# PIC-adresseur_-_SuperCAST.net
KiCad netlist of a schematic drawn in EAGLE
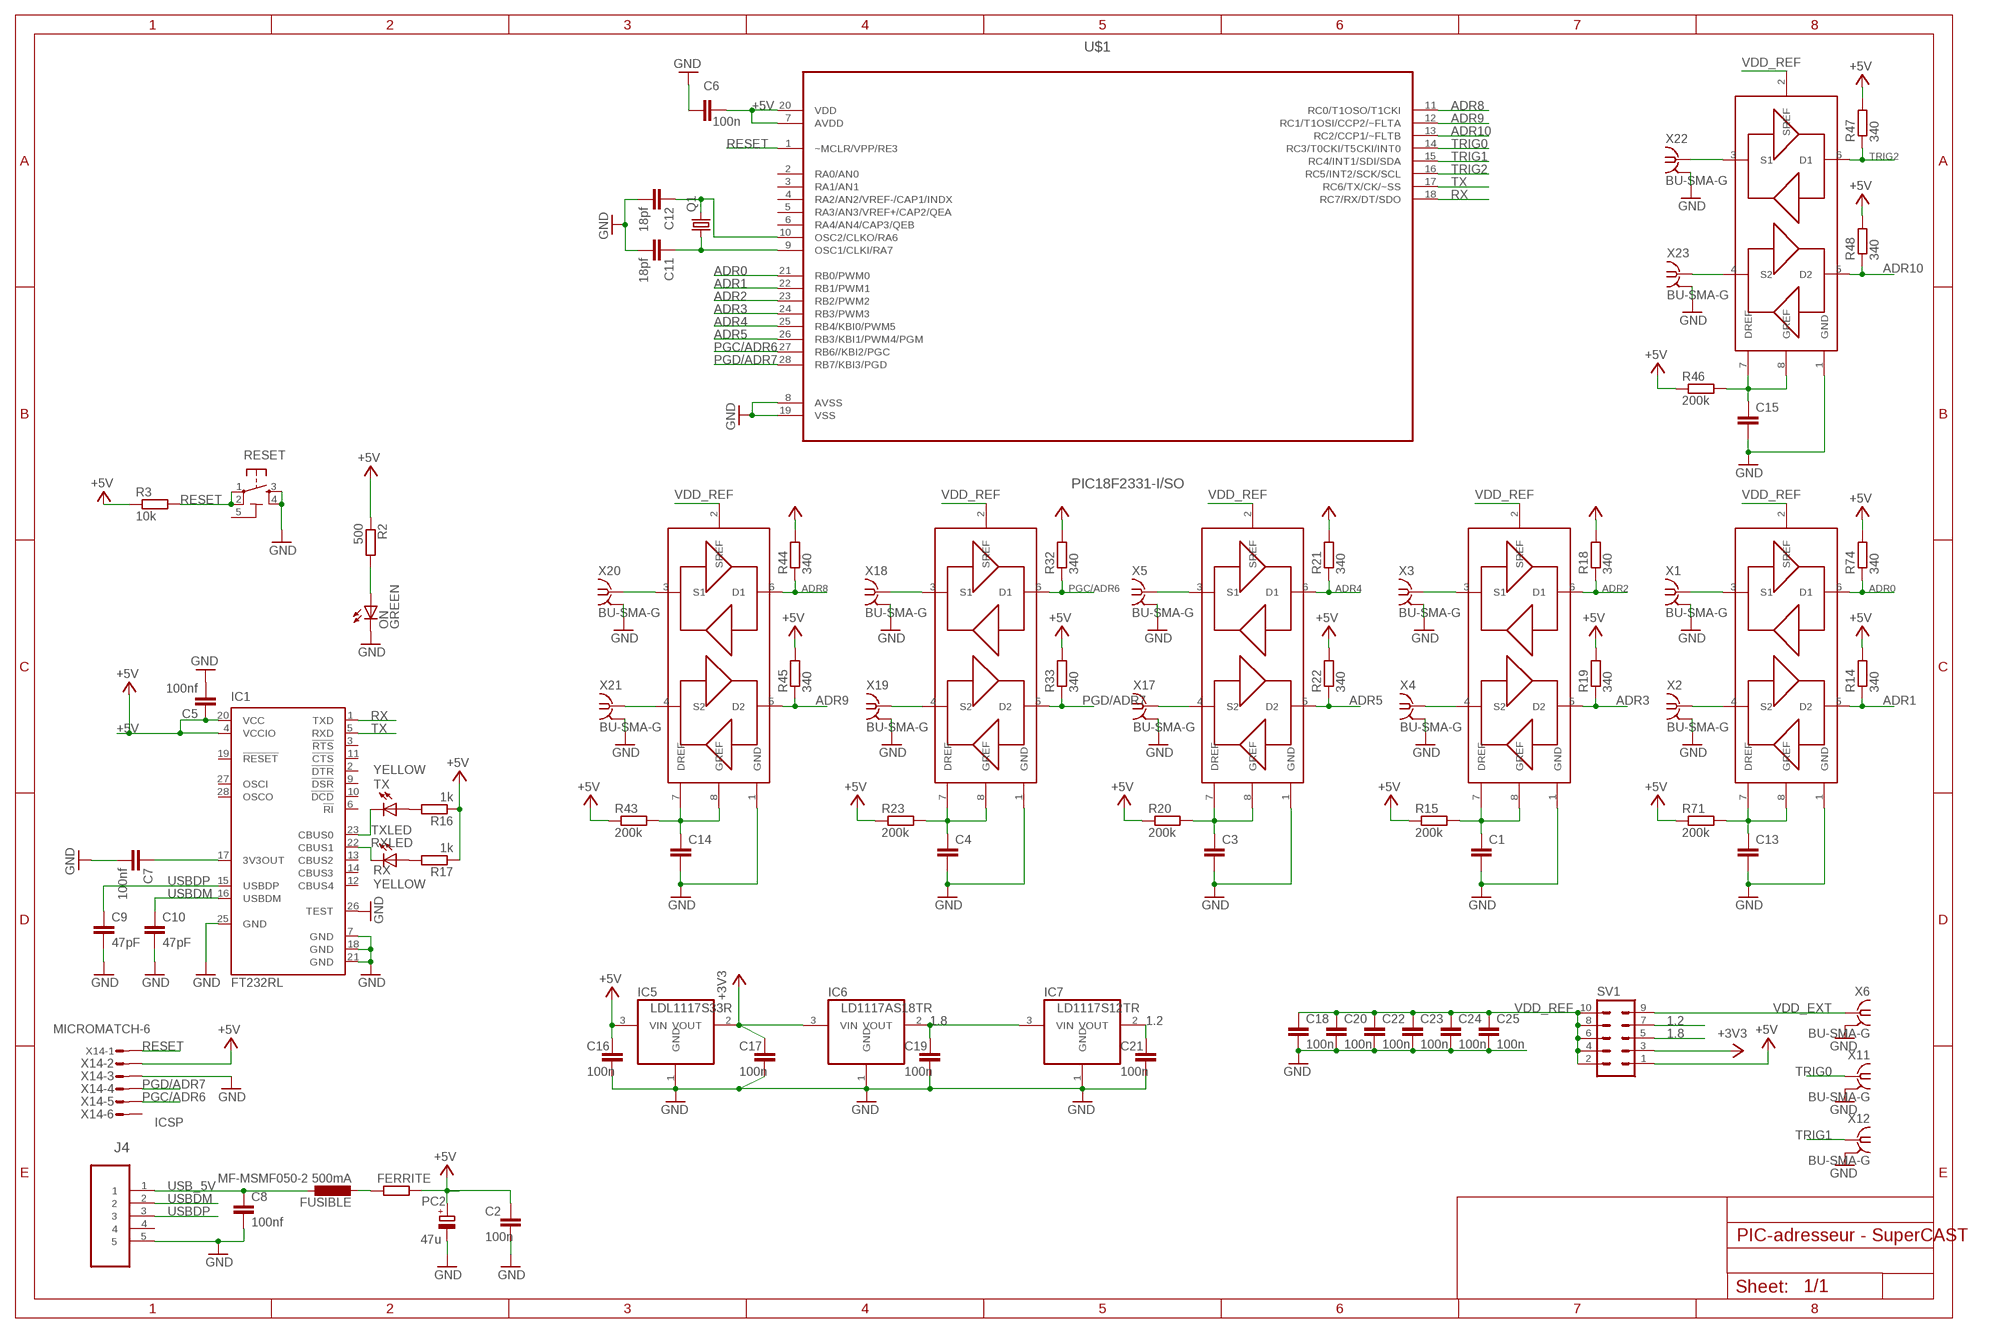
[diagram p0: schematic, sheet 1]

(export (version "E")
  (design (tool "Eeschema 10.0.6"))
  (components
    (comp (ref "C1")
      (value "C-EUC0603")
      (footprint "eagle-import:C0603")
      (libsource (lib "eagle-import") (part "rcl_334_C-EUC0603"))
    )
    (comp (ref "C2")
      (value "100n")
      (footprint "eagle-import:C0603-ROUND")
      (libsource (lib "eagle-import") (part "C-EU0603-RND"))
    )
    (comp (ref "C3")
      (value "C-EUC0603")
      (footprint "eagle-import:C0603")
      (libsource (lib "eagle-import") (part "rcl_334_C-EUC0603"))
    )
    (comp (ref "C4")
      (value "C-EUC0603")
      (footprint "eagle-import:C0603")
      (libsource (lib "eagle-import") (part "rcl_334_C-EUC0603"))
    )
    (comp (ref "C5")
      (value "100nf")
      (footprint "eagle-import:C0603")
      (libsource (lib "eagle-import") (part "C-EUC0603"))
    )
    (comp (ref "C6")
      (value "100n")
      (footprint "eagle-import:C0603K")
      (libsource (lib "eagle-import") (part "SmartPrj_C-EUC0603K"))
    )
    (comp (ref "C7")
      (value "100nf")
      (footprint "eagle-import:C0603")
      (libsource (lib "eagle-import") (part "C-EUC0603"))
    )
    (comp (ref "C8")
      (value "100nf")
      (footprint "eagle-import:C0603")
      (libsource (lib "eagle-import") (part "C-EUC0603"))
    )
    (comp (ref "C9")
      (value "47pF")
      (footprint "eagle-import:C0603")
      (libsource (lib "eagle-import") (part "C-EUC0603"))
    )
    (comp (ref "C10")
      (value "47pF")
      (footprint "eagle-import:C0603")
      (libsource (lib "eagle-import") (part "C-EUC0603"))
    )
    (comp (ref "C11")
      (value "18pf")
      (footprint "eagle-import:C0603")
      (libsource (lib "eagle-import") (part "C-EUC0603"))
    )
    (comp (ref "C12")
      (value "18pf")
      (footprint "eagle-import:C0603")
      (libsource (lib "eagle-import") (part "C-EUC0603"))
    )
    (comp (ref "C13")
      (value "C-EUC0603")
      (footprint "eagle-import:C0603")
      (libsource (lib "eagle-import") (part "rcl_334_C-EUC0603"))
    )
    (comp (ref "C14")
      (value "C-EUC0603")
      (footprint "eagle-import:C0603")
      (libsource (lib "eagle-import") (part "rcl_334_C-EUC0603"))
    )
    (comp (ref "C15")
      (value "C-EUC0603")
      (footprint "eagle-import:C0603")
      (libsource (lib "eagle-import") (part "rcl_334_C-EUC0603"))
    )
    (comp (ref "C16")
      (value "100n")
      (footprint "eagle-import:C0603-ROUND")
      (libsource (lib "eagle-import") (part "C-EU0603-RND"))
    )
    (comp (ref "C17")
      (value "100n")
      (footprint "eagle-import:C0603-ROUND")
      (libsource (lib "eagle-import") (part "C-EU0603-RND"))
    )
    (comp (ref "C18")
      (value "100n")
      (footprint "eagle-import:C0603")
      (libsource (lib "eagle-import") (part "C-EUC0603"))
    )
    (comp (ref "C19")
      (value "100n")
      (footprint "eagle-import:C0603-ROUND")
      (libsource (lib "eagle-import") (part "C-EU0603-RND"))
    )
    (comp (ref "C20")
      (value "100n")
      (footprint "eagle-import:C0603")
      (libsource (lib "eagle-import") (part "C-EUC0603"))
    )
    (comp (ref "C21")
      (value "100n")
      (footprint "eagle-import:C0603-ROUND")
      (libsource (lib "eagle-import") (part "C-EU0603-RND"))
    )
    (comp (ref "C22")
      (value "100n")
      (footprint "eagle-import:C0603")
      (libsource (lib "eagle-import") (part "C-EUC0603"))
    )
    (comp (ref "C23")
      (value "100n")
      (footprint "eagle-import:C0603")
      (libsource (lib "eagle-import") (part "C-EUC0603"))
    )
    (comp (ref "C24")
      (value "100n")
      (footprint "eagle-import:C0603")
      (libsource (lib "eagle-import") (part "C-EUC0603"))
    )
    (comp (ref "C25")
      (value "100n")
      (footprint "eagle-import:C0603")
      (libsource (lib "eagle-import") (part "C-EUC0603"))
    )
    (comp (ref "FERRITE")
      (value "R-EU_M0805")
      (footprint "eagle-import:M0805")
      (libsource (lib "eagle-import") (part "R-EU_M0805"))
    )
    (comp (ref "FUSIBLE")
      (value "MF-MSMF050-2 500mA")
      (footprint "eagle-import:L1812")
      (libsource (lib "eagle-import") (part "L-EUL1812"))
    )
    (comp (ref "IC1")
      (value "FT232RL")
      (footprint "eagle-import:SSOP28")
      (libsource (lib "eagle-import") (part "FT232RL"))
    )
    (comp (ref "IC5")
      (value "LDL1117S33R")
      (footprint "eagle-import:SOT223")
      (fields (field (name "MPN") "REG1117") (field (name "OC_FARNELL") "2729708"))
      (libsource (lib "eagle-import") (part "REG1117"))
    )
    (comp (ref "IC6")
      (value "LD1117AS18TR")
      (footprint "eagle-import:SOT223")
      (fields (field (name "MPN") "REG1117") (field (name "OC_FARNELL") "1467775"))
      (libsource (lib "eagle-import") (part "REG1117"))
    )
    (comp (ref "IC7")
      (value "LD1117S12TR")
      (footprint "eagle-import:SOT223")
      (fields (field (name "MPN") "REG1117") (field (name "OC_FARNELL") "1467778"))
      (libsource (lib "eagle-import") (part "REG1117"))
    )
    (comp (ref "J4")
      (value "47346-0001")
      (footprint "eagle-import:MOLEX_47346-0001")
      (libsource (lib "eagle-import") (part "47346-0001"))
    )
    (comp (ref "LV_LVLC1")
      (value "GTL2002DP_118")
      (footprint "eagle-import:GTL2002DP_118")
      (libsource (lib "eagle-import") (part "GTL2002DP_118"))
    )
    (comp (ref "LV_LVLC2")
      (value "GTL2002DP_118")
      (footprint "eagle-import:GTL2002DP_118")
      (libsource (lib "eagle-import") (part "GTL2002DP_118"))
    )
    (comp (ref "LV_LVLC3")
      (value "GTL2002DP_118")
      (footprint "eagle-import:GTL2002DP_118")
      (libsource (lib "eagle-import") (part "GTL2002DP_118"))
    )
    (comp (ref "LV_LVLC4")
      (value "GTL2002DP_118")
      (footprint "eagle-import:GTL2002DP_118")
      (libsource (lib "eagle-import") (part "GTL2002DP_118"))
    )
    (comp (ref "LV_LVLC5")
      (value "GTL2002DP_118")
      (footprint "eagle-import:GTL2002DP_118")
      (libsource (lib "eagle-import") (part "GTL2002DP_118"))
    )
    (comp (ref "LV_LVLC6")
      (value "GTL2002DP_118")
      (footprint "eagle-import:GTL2002DP_118")
      (libsource (lib "eagle-import") (part "GTL2002DP_118"))
    )
    (comp (ref "ON")
      (value "GREEN")
      (footprint "eagle-import:CHIP-LED0805")
      (libsource (lib "eagle-import") (part "LEDCHIP-LED0805"))
    )
    (comp (ref "PC2")
      (value "47u")
      (footprint "eagle-import:PANASONIC_D")
      (libsource (lib "eagle-import") (part "CPOL-EUD"))
    )
    (comp (ref "Q1")
      (value "CRYSTALSM49")
      (footprint "eagle-import:SM49")
      (fields (field (name "OC_FARNELL") "1842273"))
      (libsource (lib "eagle-import") (part "CRYSTALSM49"))
    )
    (comp (ref "R2")
      (value "500")
      (footprint "eagle-import:R0603")
      (libsource (lib "eagle-import") (part "R-EU_R0603"))
    )
    (comp (ref "R3")
      (value "10k")
      (footprint "eagle-import:R0603")
      (libsource (lib "eagle-import") (part "R-EU_R0603"))
    )
    (comp (ref "R14")
      (value "340")
      (footprint "eagle-import:R0603")
      (libsource (lib "eagle-import") (part "rcl_334_R-EU_R0603"))
    )
    (comp (ref "R15")
      (value "200k")
      (footprint "eagle-import:R0603")
      (libsource (lib "eagle-import") (part "rcl_334_R-EU_R0603"))
    )
    (comp (ref "R16")
      (value "1k")
      (footprint "eagle-import:R0603")
      (libsource (lib "eagle-import") (part "R-EU_R0603"))
    )
    (comp (ref "R17")
      (value "1k")
      (footprint "eagle-import:R0603")
      (libsource (lib "eagle-import") (part "R-EU_R0603"))
    )
    (comp (ref "R18")
      (value "340")
      (footprint "eagle-import:R0603")
      (libsource (lib "eagle-import") (part "rcl_334_R-EU_R0603"))
    )
    (comp (ref "R19")
      (value "340")
      (footprint "eagle-import:R0603")
      (libsource (lib "eagle-import") (part "rcl_334_R-EU_R0603"))
    )
    (comp (ref "R20")
      (value "200k")
      (footprint "eagle-import:R0603")
      (libsource (lib "eagle-import") (part "rcl_334_R-EU_R0603"))
    )
    (comp (ref "R21")
      (value "340")
      (footprint "eagle-import:R0603")
      (libsource (lib "eagle-import") (part "rcl_334_R-EU_R0603"))
    )
    (comp (ref "R22")
      (value "340")
      (footprint "eagle-import:R0603")
      (libsource (lib "eagle-import") (part "rcl_334_R-EU_R0603"))
    )
    (comp (ref "R23")
      (value "200k")
      (footprint "eagle-import:R0603")
      (libsource (lib "eagle-import") (part "rcl_334_R-EU_R0603"))
    )
    (comp (ref "R32")
      (value "340")
      (footprint "eagle-import:R0603")
      (libsource (lib "eagle-import") (part "rcl_334_R-EU_R0603"))
    )
    (comp (ref "R33")
      (value "340")
      (footprint "eagle-import:R0603")
      (libsource (lib "eagle-import") (part "rcl_334_R-EU_R0603"))
    )
    (comp (ref "R43")
      (value "200k")
      (footprint "eagle-import:R0603")
      (libsource (lib "eagle-import") (part "rcl_334_R-EU_R0603"))
    )
    (comp (ref "R44")
      (value "340")
      (footprint "eagle-import:R0603")
      (libsource (lib "eagle-import") (part "rcl_334_R-EU_R0603"))
    )
    (comp (ref "R45")
      (value "340")
      (footprint "eagle-import:R0603")
      (libsource (lib "eagle-import") (part "rcl_334_R-EU_R0603"))
    )
    (comp (ref "R46")
      (value "200k")
      (footprint "eagle-import:R0603")
      (libsource (lib "eagle-import") (part "rcl_334_R-EU_R0603"))
    )
    (comp (ref "R47")
      (value "340")
      (footprint "eagle-import:R0603")
      (libsource (lib "eagle-import") (part "rcl_334_R-EU_R0603"))
    )
    (comp (ref "R48")
      (value "340")
      (footprint "eagle-import:R0603")
      (libsource (lib "eagle-import") (part "rcl_334_R-EU_R0603"))
    )
    (comp (ref "R71")
      (value "200k")
      (footprint "eagle-import:R0603")
      (libsource (lib "eagle-import") (part "rcl_334_R-EU_R0603"))
    )
    (comp (ref "R74")
      (value "340")
      (footprint "eagle-import:R0603")
      (libsource (lib "eagle-import") (part "rcl_334_R-EU_R0603"))
    )
    (comp (ref "RESET")
      (value "TS42031-160R-TR-7260")
      (footprint "eagle-import:TS42")
      (libsource (lib "eagle-import") (part "TS42"))
    )
    (comp (ref "RX")
      (value "YELLOW")
      (footprint "eagle-import:CHIP-LED0805")
      (libsource (lib "eagle-import") (part "LEDCHIP-LED0805"))
    )
    (comp (ref "SV1")
      (value "MA05-2")
      (footprint "eagle-import:MA05-2")
      (libsource (lib "eagle-import") (part "MA05-2"))
    )
    (comp (ref "TX")
      (value "YELLOW")
      (footprint "eagle-import:CHIP-LED0805")
      (libsource (lib "eagle-import") (part "LEDCHIP-LED0805"))
    )
    (comp (ref "U$1")
      (value "PIC18F2331-I/SO")
      (footprint "eagle-import:SOIC127P1030X265-28N")
      (libsource (lib "eagle-import") (part "PIC18F2331-I/SO"))
    )
    (comp (ref "X1")
      (value "BU-SMA-G")
      (footprint "eagle-import:BU-SMA-G")
      (fields (field (name "OC_FARNELL") "1248989"))
      (libsource (lib "eagle-import") (part "BU-SMA-G"))
    )
    (comp (ref "X2")
      (value "BU-SMA-G")
      (footprint "eagle-import:BU-SMA-G")
      (fields (field (name "OC_FARNELL") "1248989"))
      (libsource (lib "eagle-import") (part "BU-SMA-G"))
    )
    (comp (ref "X3")
      (value "BU-SMA-G")
      (footprint "eagle-import:BU-SMA-G")
      (fields (field (name "OC_FARNELL") "1248989"))
      (libsource (lib "eagle-import") (part "BU-SMA-G"))
    )
    (comp (ref "X4")
      (value "BU-SMA-G")
      (footprint "eagle-import:BU-SMA-G")
      (fields (field (name "OC_FARNELL") "1248989"))
      (libsource (lib "eagle-import") (part "BU-SMA-G"))
    )
    (comp (ref "X5")
      (value "BU-SMA-G")
      (footprint "eagle-import:BU-SMA-G")
      (fields (field (name "OC_FARNELL") "1248989"))
      (libsource (lib "eagle-import") (part "BU-SMA-G"))
    )
    (comp (ref "X6")
      (value "BU-SMA-G")
      (footprint "eagle-import:BU-SMA-G")
      (fields (field (name "OC_FARNELL") "1248989"))
      (libsource (lib "eagle-import") (part "BU-SMA-G"))
    )
    (comp (ref "X11")
      (value "BU-SMA-G")
      (footprint "eagle-import:BU-SMA-G")
      (fields (field (name "OC_FARNELL") "1248989"))
      (libsource (lib "eagle-import") (part "BU-SMA-G"))
    )
    (comp (ref "X12")
      (value "BU-SMA-G")
      (footprint "eagle-import:BU-SMA-G")
      (fields (field (name "OC_FARNELL") "1248989"))
      (libsource (lib "eagle-import") (part "BU-SMA-G"))
    )
    (comp (ref "X14")
      (value "MICROMATCH-6")
      (footprint "eagle-import:MICROMATCH-6")
      (fields (field (name "MPN") "7-215464-6"))
      (libsource (lib "eagle-import") (part "MICROMATCH-6"))
    )
    (comp (ref "X17")
      (value "BU-SMA-G")
      (footprint "eagle-import:BU-SMA-G")
      (fields (field (name "OC_FARNELL") "1248989"))
      (libsource (lib "eagle-import") (part "BU-SMA-G"))
    )
    (comp (ref "X18")
      (value "BU-SMA-G")
      (footprint "eagle-import:BU-SMA-G")
      (fields (field (name "OC_FARNELL") "1248989"))
      (libsource (lib "eagle-import") (part "BU-SMA-G"))
    )
    (comp (ref "X19")
      (value "BU-SMA-G")
      (footprint "eagle-import:BU-SMA-G")
      (fields (field (name "OC_FARNELL") "1248989"))
      (libsource (lib "eagle-import") (part "BU-SMA-G"))
    )
    (comp (ref "X20")
      (value "BU-SMA-G")
      (footprint "eagle-import:BU-SMA-G")
      (fields (field (name "OC_FARNELL") "1248989"))
      (libsource (lib "eagle-import") (part "BU-SMA-G"))
    )
    (comp (ref "X21")
      (value "BU-SMA-G")
      (footprint "eagle-import:BU-SMA-G")
      (fields (field (name "OC_FARNELL") "1248989"))
      (libsource (lib "eagle-import") (part "BU-SMA-G"))
    )
    (comp (ref "X22")
      (value "BU-SMA-G")
      (footprint "eagle-import:BU-SMA-G")
      (fields (field (name "OC_FARNELL") "1248989"))
      (libsource (lib "eagle-import") (part "BU-SMA-G"))
    )
    (comp (ref "X23")
      (value "BU-SMA-G")
      (footprint "eagle-import:BU-SMA-G")
      (fields (field (name "OC_FARNELL") "1248989"))
      (libsource (lib "eagle-import") (part "BU-SMA-G"))
    )
  )
  (nets
    (net (code "1") (name "+3V3") (class "Default")
      (node (ref "C17") (pin "2") (pinfunction "2_2") (pintype "passive"))
      (node (ref "IC5") (pin "2") (pinfunction "VOUT_2") (pintype "output"))
      (node (ref "IC6") (pin "3") (pinfunction "VIN_3") (pintype "input"))
      (node (ref "SV1") (pin "3") (pinfunction "3_3") (pintype "passive"))
    )
    (net (code "2") (name "+5V") (class "Default")
      (node (ref "C16") (pin "2") (pinfunction "2_2") (pintype "passive"))
      (node (ref "C2") (pin "2") (pinfunction "2_2") (pintype "passive"))
      (node (ref "C5") (pin "1") (pinfunction "1_1") (pintype "passive"))
      (node (ref "C6") (pin "2") (pinfunction "2_2") (pintype "passive"))
      (node (ref "FERRITE") (pin "2") (pinfunction "2_2") (pintype "passive"))
      (node (ref "IC1") (pin "20") (pinfunction "VCC_20") (pintype "power_in"))
      (node (ref "IC1") (pin "4") (pinfunction "VCCIO_4") (pintype "power_in"))
      (node (ref "IC5") (pin "3") (pinfunction "VIN_3") (pintype "input"))
      (node (ref "PC2") (pin "+") (pinfunction "+_+") (pintype "passive"))
      (node (ref "R14") (pin "2") (pinfunction "2_2") (pintype "passive"))
      (node (ref "R15") (pin "1") (pinfunction "1_1") (pintype "passive"))
      (node (ref "R16") (pin "1") (pinfunction "1_1") (pintype "passive"))
      (node (ref "R17") (pin "1") (pinfunction "1_1") (pintype "passive"))
      (node (ref "R18") (pin "2") (pinfunction "2_2") (pintype "passive"))
      (node (ref "R19") (pin "2") (pinfunction "2_2") (pintype "passive"))
      (node (ref "R2") (pin "1") (pinfunction "1_1") (pintype "passive"))
      (node (ref "R20") (pin "1") (pinfunction "1_1") (pintype "passive"))
      (node (ref "R21") (pin "2") (pinfunction "2_2") (pintype "passive"))
      (node (ref "R22") (pin "2") (pinfunction "2_2") (pintype "passive"))
      (node (ref "R23") (pin "1") (pinfunction "1_1") (pintype "passive"))
      (node (ref "R3") (pin "1") (pinfunction "1_1") (pintype "passive"))
      (node (ref "R32") (pin "2") (pinfunction "2_2") (pintype "passive"))
      (node (ref "R33") (pin "2") (pinfunction "2_2") (pintype "passive"))
      (node (ref "R43") (pin "1") (pinfunction "1_1") (pintype "passive"))
      (node (ref "R44") (pin "2") (pinfunction "2_2") (pintype "passive"))
      (node (ref "R45") (pin "2") (pinfunction "2_2") (pintype "passive"))
      (node (ref "R46") (pin "1") (pinfunction "1_1") (pintype "passive"))
      (node (ref "R47") (pin "2") (pinfunction "2_2") (pintype "passive"))
      (node (ref "R48") (pin "2") (pinfunction "2_2") (pintype "passive"))
      (node (ref "R71") (pin "1") (pinfunction "1_1") (pintype "passive"))
      (node (ref "R74") (pin "2") (pinfunction "2_2") (pintype "passive"))
      (node (ref "SV1") (pin "1") (pinfunction "1_1") (pintype "passive"))
      (node (ref "U$1") (pin "20") (pinfunction "VDD_20") (pintype "power_in"))
      (node (ref "U$1") (pin "7") (pinfunction "AVDD_7") (pintype "power_in"))
      (node (ref "X14") (pin "2") (pinfunction "S_2") (pintype "passive"))
    )
    (net (code "3") (name "/1.2") (class "Default")
      (node (ref "C21") (pin "2") (pinfunction "2_2") (pintype "passive"))
      (node (ref "IC7") (pin "2") (pinfunction "VOUT_2") (pintype "output"))
      (node (ref "SV1") (pin "7") (pinfunction "7_7") (pintype "passive"))
    )
    (net (code "4") (name "/1.8") (class "Default")
      (node (ref "C19") (pin "2") (pinfunction "2_2") (pintype "passive"))
      (node (ref "IC6") (pin "2") (pinfunction "VOUT_2") (pintype "output"))
      (node (ref "IC7") (pin "3") (pinfunction "VIN_3") (pintype "input"))
      (node (ref "SV1") (pin "5") (pinfunction "5_5") (pintype "passive"))
    )
    (net (code "5") (name "/5-GND") (class "Default")
      (node (ref "RESET") (pin "5") (pinfunction "5-GND_5") (pintype "power_in"))
    )
    (net (code "6") (name "/ADR0") (class "Default")
      (node (ref "LV_LVLC2") (pin "6") (pinfunction "D1_6") (pintype "bidirectional"))
      (node (ref "R74") (pin "1") (pinfunction "1_1") (pintype "passive"))
      (node (ref "U$1") (pin "21") (pinfunction "RB0/PWM0_21") (pintype "bidirectional"))
    )
    (net (code "7") (name "/ADR1") (class "Default")
      (node (ref "LV_LVLC2") (pin "5") (pinfunction "D2_5") (pintype "bidirectional"))
      (node (ref "R14") (pin "1") (pinfunction "1_1") (pintype "passive"))
      (node (ref "U$1") (pin "22") (pinfunction "RB1/PWM1_22") (pintype "bidirectional"))
    )
    (net (code "8") (name "/ADR2") (class "Default")
      (node (ref "LV_LVLC1") (pin "6") (pinfunction "D1_6") (pintype "bidirectional"))
      (node (ref "R18") (pin "1") (pinfunction "1_1") (pintype "passive"))
      (node (ref "U$1") (pin "23") (pinfunction "RB2/PWM2_23") (pintype "bidirectional"))
    )
    (net (code "9") (name "/ADR3") (class "Default")
      (node (ref "LV_LVLC1") (pin "5") (pinfunction "D2_5") (pintype "bidirectional"))
      (node (ref "R19") (pin "1") (pinfunction "1_1") (pintype "passive"))
      (node (ref "U$1") (pin "24") (pinfunction "RB3/PWM3_24") (pintype "bidirectional"))
    )
    (net (code "10") (name "/ADR4") (class "Default")
      (node (ref "LV_LVLC3") (pin "6") (pinfunction "D1_6") (pintype "bidirectional"))
      (node (ref "R21") (pin "1") (pinfunction "1_1") (pintype "passive"))
      (node (ref "U$1") (pin "25") (pinfunction "RB4/KBI0/PWM5_25") (pintype "bidirectional"))
    )
    (net (code "11") (name "/ADR5") (class "Default")
      (node (ref "LV_LVLC3") (pin "5") (pinfunction "D2_5") (pintype "bidirectional"))
      (node (ref "R22") (pin "1") (pinfunction "1_1") (pintype "passive"))
      (node (ref "U$1") (pin "26") (pinfunction "RB3/KBI1/PWM4/PGM_26") (pintype "bidirectional"))
    )
    (net (code "12") (name "/ADR8") (class "Default")
      (node (ref "LV_LVLC5") (pin "6") (pinfunction "D1_6") (pintype "bidirectional"))
      (node (ref "R44") (pin "1") (pinfunction "1_1") (pintype "passive"))
      (node (ref "U$1") (pin "11") (pinfunction "RC0/T1OSO/T1CKI_11") (pintype "bidirectional"))
    )
    (net (code "13") (name "/ADR9") (class "Default")
      (node (ref "LV_LVLC5") (pin "5") (pinfunction "D2_5") (pintype "bidirectional"))
      (node (ref "R45") (pin "1") (pinfunction "1_1") (pintype "passive"))
      (node (ref "U$1") (pin "12") (pinfunction "RC1/T1OSI/CCP2/~{FLTA}_12") (pintype "bidirectional"))
    )
    (net (code "14") (name "/ADR10") (class "Default")
      (node (ref "LV_LVLC6") (pin "5") (pinfunction "D2_5") (pintype "bidirectional"))
      (node (ref "R48") (pin "1") (pinfunction "1_1") (pintype "passive"))
      (node (ref "U$1") (pin "13") (pinfunction "RC2/CCP1/~{FLTB}_13") (pintype "bidirectional"))
    )
    (net (code "15") (name "/PGC{slash}ADR6") (class "Default")
      (node (ref "LV_LVLC4") (pin "6") (pinfunction "D1_6") (pintype "bidirectional"))
      (node (ref "R32") (pin "1") (pinfunction "1_1") (pintype "passive"))
      (node (ref "U$1") (pin "27") (pinfunction "RB6//KBI2/PGC_27") (pintype "bidirectional"))
      (node (ref "X14") (pin "5") (pinfunction "S_5") (pintype "passive"))
    )
    (net (code "16") (name "/PGD{slash}ADR7") (class "Default")
      (node (ref "LV_LVLC4") (pin "5") (pinfunction "D2_5") (pintype "bidirectional"))
      (node (ref "R33") (pin "1") (pinfunction "1_1") (pintype "passive"))
      (node (ref "U$1") (pin "28") (pinfunction "RB7/KBI3/PGD_28") (pintype "bidirectional"))
      (node (ref "X14") (pin "4") (pinfunction "S_4") (pintype "passive"))
    )
    (net (code "17") (name "/RESET") (class "Default")
      (node (ref "R3") (pin "2") (pinfunction "2_2") (pintype "passive"))
      (node (ref "RESET") (pin "1") (pinfunction "1_1") (pintype "passive"))
      (node (ref "RESET") (pin "2") (pinfunction "2_2") (pintype "passive"))
      (node (ref "U$1") (pin "1") (pinfunction "~{MCLR/VPP/RE3}_1") (pintype "input"))
      (node (ref "X14") (pin "1") (pinfunction "S_1") (pintype "passive"))
    )
    (net (code "18") (name "/RX") (class "Default")
      (node (ref "IC1") (pin "1") (pinfunction "TXD_1") (pintype "output"))
      (node (ref "U$1") (pin "18") (pinfunction "RC7/RX/DT/SDO_18") (pintype "bidirectional"))
    )
    (net (code "19") (name "/RXLED") (class "Default")
      (node (ref "IC1") (pin "22") (pinfunction "CBUS1_22") (pintype "bidirectional"))
      (node (ref "RX") (pin "C") (pinfunction "C_C") (pintype "passive"))
    )
    (net (code "20") (name "/TRIG0") (class "Default")
      (node (ref "U$1") (pin "14") (pinfunction "RC3/T0CKI/T5CKI/INT0_14") (pintype "bidirectional"))
      (node (ref "X11") (pin "1") (pinfunction "1_1") (pintype "passive"))
    )
    (net (code "21") (name "/TRIG1") (class "Default")
      (node (ref "U$1") (pin "15") (pinfunction "RC4/INT1/SDI/SDA_15") (pintype "bidirectional"))
      (node (ref "X12") (pin "1") (pinfunction "1_1") (pintype "passive"))
    )
    (net (code "22") (name "/TRIG2") (class "Default")
      (node (ref "LV_LVLC6") (pin "6") (pinfunction "D1_6") (pintype "bidirectional"))
      (node (ref "R47") (pin "1") (pinfunction "1_1") (pintype "passive"))
      (node (ref "U$1") (pin "16") (pinfunction "RC5/INT2/SCK/SCL_16") (pintype "bidirectional"))
    )
    (net (code "23") (name "/TX") (class "Default")
      (node (ref "IC1") (pin "5") (pinfunction "RXD_5") (pintype "input"))
      (node (ref "U$1") (pin "17") (pinfunction "RC6/TX/CK/~{SS}_17") (pintype "bidirectional"))
    )
    (net (code "24") (name "/TXLED") (class "Default")
      (node (ref "IC1") (pin "23") (pinfunction "CBUS0_23") (pintype "bidirectional"))
      (node (ref "TX") (pin "C") (pinfunction "C_C") (pintype "passive"))
    )
    (net (code "25") (name "/USBDM") (class "Default")
      (node (ref "C10") (pin "1") (pinfunction "1_1") (pintype "passive"))
      (node (ref "IC1") (pin "16") (pinfunction "USBDM_16") (pintype "bidirectional"))
      (node (ref "J4") (pin "2") (pinfunction "2_2") (pintype "input"))
    )
    (net (code "26") (name "/USBDP") (class "Default")
      (node (ref "C9") (pin "1") (pinfunction "1_1") (pintype "passive"))
      (node (ref "IC1") (pin "15") (pinfunction "USBDP_15") (pintype "bidirectional"))
      (node (ref "J4") (pin "3") (pinfunction "3_3") (pintype "input"))
    )
    (net (code "27") (name "/USB_5V") (class "Default")
      (node (ref "C8") (pin "1") (pinfunction "1_1") (pintype "passive"))
      (node (ref "FUSIBLE") (pin "1") (pinfunction "1_1") (pintype "passive"))
      (node (ref "J4") (pin "1") (pinfunction "1_1") (pintype "input"))
    )
    (net (code "28") (name "/VDD_EXT") (class "Default")
      (node (ref "SV1") (pin "9") (pinfunction "9_9") (pintype "passive"))
      (node (ref "X6") (pin "1") (pinfunction "1_1") (pintype "passive"))
    )
    (net (code "29") (name "/VDD_REF") (class "Default")
      (node (ref "C18") (pin "1") (pinfunction "1_1") (pintype "passive"))
      (node (ref "C20") (pin "1") (pinfunction "1_1") (pintype "passive"))
      (node (ref "C22") (pin "1") (pinfunction "1_1") (pintype "passive"))
      (node (ref "C23") (pin "1") (pinfunction "1_1") (pintype "passive"))
      (node (ref "C24") (pin "1") (pinfunction "1_1") (pintype "passive"))
      (node (ref "C25") (pin "1") (pinfunction "1_1") (pintype "passive"))
      (node (ref "LV_LVLC1") (pin "2") (pinfunction "SREF_2") (pintype "bidirectional"))
      (node (ref "LV_LVLC2") (pin "2") (pinfunction "SREF_2") (pintype "bidirectional"))
      (node (ref "LV_LVLC3") (pin "2") (pinfunction "SREF_2") (pintype "bidirectional"))
      (node (ref "LV_LVLC4") (pin "2") (pinfunction "SREF_2") (pintype "bidirectional"))
      (node (ref "LV_LVLC5") (pin "2") (pinfunction "SREF_2") (pintype "bidirectional"))
      (node (ref "LV_LVLC6") (pin "2") (pinfunction "SREF_2") (pintype "bidirectional"))
      (node (ref "SV1") (pin "10") (pinfunction "10_10") (pintype "passive"))
      (node (ref "SV1") (pin "2") (pinfunction "2_2") (pintype "passive"))
      (node (ref "SV1") (pin "4") (pinfunction "4_4") (pintype "passive"))
      (node (ref "SV1") (pin "6") (pinfunction "6_6") (pintype "passive"))
      (node (ref "SV1") (pin "8") (pinfunction "8_8") (pintype "passive"))
    )
    (net (code "30") (name "GND") (class "Default")
      (node (ref "C1") (pin "2") (pinfunction "2_2") (pintype "passive"))
      (node (ref "C10") (pin "2") (pinfunction "2_2") (pintype "passive"))
      (node (ref "C11") (pin "2") (pinfunction "2_2") (pintype "passive"))
      (node (ref "C12") (pin "2") (pinfunction "2_2") (pintype "passive"))
      (node (ref "C13") (pin "2") (pinfunction "2_2") (pintype "passive"))
      (node (ref "C14") (pin "2") (pinfunction "2_2") (pintype "passive"))
      (node (ref "C15") (pin "2") (pinfunction "2_2") (pintype "passive"))
      (node (ref "C16") (pin "1") (pinfunction "1_1") (pintype "passive"))
      (node (ref "C17") (pin "1") (pinfunction "1_1") (pintype "passive"))
      (node (ref "C18") (pin "2") (pinfunction "2_2") (pintype "passive"))
      (node (ref "C19") (pin "1") (pinfunction "1_1") (pintype "passive"))
      (node (ref "C2") (pin "1") (pinfunction "1_1") (pintype "passive"))
      (node (ref "C20") (pin "2") (pinfunction "2_2") (pintype "passive"))
      (node (ref "C21") (pin "1") (pinfunction "1_1") (pintype "passive"))
      (node (ref "C22") (pin "2") (pinfunction "2_2") (pintype "passive"))
      (node (ref "C23") (pin "2") (pinfunction "2_2") (pintype "passive"))
      (node (ref "C24") (pin "2") (pinfunction "2_2") (pintype "passive"))
      (node (ref "C25") (pin "2") (pinfunction "2_2") (pintype "passive"))
      (node (ref "C3") (pin "2") (pinfunction "2_2") (pintype "passive"))
      (node (ref "C4") (pin "2") (pinfunction "2_2") (pintype "passive"))
      (node (ref "C5") (pin "2") (pinfunction "2_2") (pintype "passive"))
      (node (ref "C6") (pin "1") (pinfunction "1_1") (pintype "passive"))
      (node (ref "C7") (pin "2") (pinfunction "2_2") (pintype "passive"))
      (node (ref "C8") (pin "2") (pinfunction "2_2") (pintype "passive"))
      (node (ref "C9") (pin "2") (pinfunction "2_2") (pintype "passive"))
      (node (ref "IC1") (pin "18") (pinfunction "GND_18") (pintype "power_in"))
      (node (ref "IC1") (pin "21") (pinfunction "GND_21") (pintype "power_in"))
      (node (ref "IC1") (pin "25") (pinfunction "GND_25") (pintype "power_in"))
      (node (ref "IC1") (pin "26") (pinfunction "TEST_26") (pintype "input"))
      (node (ref "IC1") (pin "7") (pinfunction "GND_7") (pintype "power_in"))
      (node (ref "IC5") (pin "1") (pinfunction "GND_1") (pintype "power_in"))
      (node (ref "IC6") (pin "1") (pinfunction "GND_1") (pintype "power_in"))
      (node (ref "IC7") (pin "1") (pinfunction "GND_1") (pintype "power_in"))
      (node (ref "J4") (pin "5") (pinfunction "5_5") (pintype "input"))
      (node (ref "LV_LVLC1") (pin "1") (pinfunction "GND_1") (pintype "bidirectional"))
      (node (ref "LV_LVLC2") (pin "1") (pinfunction "GND_1") (pintype "bidirectional"))
      (node (ref "LV_LVLC3") (pin "1") (pinfunction "GND_1") (pintype "bidirectional"))
      (node (ref "LV_LVLC4") (pin "1") (pinfunction "GND_1") (pintype "bidirectional"))
      (node (ref "LV_LVLC5") (pin "1") (pinfunction "GND_1") (pintype "bidirectional"))
      (node (ref "LV_LVLC6") (pin "1") (pinfunction "GND_1") (pintype "bidirectional"))
      (node (ref "ON") (pin "C") (pinfunction "C_C") (pintype "passive"))
      (node (ref "PC2") (pin "-") (pinfunction "-_-") (pintype "passive"))
      (node (ref "RESET") (pin "3") (pinfunction "3_3") (pintype "passive"))
      (node (ref "RESET") (pin "4") (pinfunction "4_4") (pintype "passive"))
      (node (ref "U$1") (pin "19") (pinfunction "VSS_19") (pintype "passive"))
      (node (ref "U$1") (pin "8") (pinfunction "AVSS_8") (pintype "passive"))
      (node (ref "X1") (pin "2") (pinfunction "2_2") (pintype "passive"))
      (node (ref "X1") (pin "3") (pinfunction "2_3") (pintype "passive"))
      (node (ref "X1") (pin "4") (pinfunction "2_4") (pintype "passive"))
      (node (ref "X1") (pin "5") (pinfunction "2_5") (pintype "passive"))
      (node (ref "X11") (pin "2") (pinfunction "2_2") (pintype "passive"))
      (node (ref "X11") (pin "3") (pinfunction "2_3") (pintype "passive"))
      (node (ref "X11") (pin "4") (pinfunction "2_4") (pintype "passive"))
      (node (ref "X11") (pin "5") (pinfunction "2_5") (pintype "passive"))
      (node (ref "X12") (pin "2") (pinfunction "2_2") (pintype "passive"))
      (node (ref "X12") (pin "3") (pinfunction "2_3") (pintype "passive"))
      (node (ref "X12") (pin "4") (pinfunction "2_4") (pintype "passive"))
      (node (ref "X12") (pin "5") (pinfunction "2_5") (pintype "passive"))
      (node (ref "X14") (pin "3") (pinfunction "S_3") (pintype "passive"))
      (node (ref "X17") (pin "2") (pinfunction "2_2") (pintype "passive"))
      (node (ref "X17") (pin "3") (pinfunction "2_3") (pintype "passive"))
      (node (ref "X17") (pin "4") (pinfunction "2_4") (pintype "passive"))
      (node (ref "X17") (pin "5") (pinfunction "2_5") (pintype "passive"))
      (node (ref "X18") (pin "2") (pinfunction "2_2") (pintype "passive"))
      (node (ref "X18") (pin "3") (pinfunction "2_3") (pintype "passive"))
      (node (ref "X18") (pin "4") (pinfunction "2_4") (pintype "passive"))
      (node (ref "X18") (pin "5") (pinfunction "2_5") (pintype "passive"))
      (node (ref "X19") (pin "2") (pinfunction "2_2") (pintype "passive"))
      (node (ref "X19") (pin "3") (pinfunction "2_3") (pintype "passive"))
      (node (ref "X19") (pin "4") (pinfunction "2_4") (pintype "passive"))
      (node (ref "X19") (pin "5") (pinfunction "2_5") (pintype "passive"))
      (node (ref "X2") (pin "2") (pinfunction "2_2") (pintype "passive"))
      (node (ref "X2") (pin "3") (pinfunction "2_3") (pintype "passive"))
      (node (ref "X2") (pin "4") (pinfunction "2_4") (pintype "passive"))
      (node (ref "X2") (pin "5") (pinfunction "2_5") (pintype "passive"))
      (node (ref "X20") (pin "2") (pinfunction "2_2") (pintype "passive"))
      (node (ref "X20") (pin "3") (pinfunction "2_3") (pintype "passive"))
      (node (ref "X20") (pin "4") (pinfunction "2_4") (pintype "passive"))
      (node (ref "X20") (pin "5") (pinfunction "2_5") (pintype "passive"))
      (node (ref "X21") (pin "2") (pinfunction "2_2") (pintype "passive"))
      (node (ref "X21") (pin "3") (pinfunction "2_3") (pintype "passive"))
      (node (ref "X21") (pin "4") (pinfunction "2_4") (pintype "passive"))
      (node (ref "X21") (pin "5") (pinfunction "2_5") (pintype "passive"))
      (node (ref "X22") (pin "2") (pinfunction "2_2") (pintype "passive"))
      (node (ref "X22") (pin "3") (pinfunction "2_3") (pintype "passive"))
      (node (ref "X22") (pin "4") (pinfunction "2_4") (pintype "passive"))
      (node (ref "X22") (pin "5") (pinfunction "2_5") (pintype "passive"))
      (node (ref "X23") (pin "2") (pinfunction "2_2") (pintype "passive"))
      (node (ref "X23") (pin "3") (pinfunction "2_3") (pintype "passive"))
      (node (ref "X23") (pin "4") (pinfunction "2_4") (pintype "passive"))
      (node (ref "X23") (pin "5") (pinfunction "2_5") (pintype "passive"))
      (node (ref "X3") (pin "2") (pinfunction "2_2") (pintype "passive"))
      (node (ref "X3") (pin "3") (pinfunction "2_3") (pintype "passive"))
      (node (ref "X3") (pin "4") (pinfunction "2_4") (pintype "passive"))
      (node (ref "X3") (pin "5") (pinfunction "2_5") (pintype "passive"))
      (node (ref "X4") (pin "2") (pinfunction "2_2") (pintype "passive"))
      (node (ref "X4") (pin "3") (pinfunction "2_3") (pintype "passive"))
      (node (ref "X4") (pin "4") (pinfunction "2_4") (pintype "passive"))
      (node (ref "X4") (pin "5") (pinfunction "2_5") (pintype "passive"))
      (node (ref "X5") (pin "2") (pinfunction "2_2") (pintype "passive"))
      (node (ref "X5") (pin "3") (pinfunction "2_3") (pintype "passive"))
      (node (ref "X5") (pin "4") (pinfunction "2_4") (pintype "passive"))
      (node (ref "X5") (pin "5") (pinfunction "2_5") (pintype "passive"))
      (node (ref "X6") (pin "2") (pinfunction "2_2") (pintype "passive"))
      (node (ref "X6") (pin "3") (pinfunction "2_3") (pintype "passive"))
      (node (ref "X6") (pin "4") (pinfunction "2_4") (pintype "passive"))
      (node (ref "X6") (pin "5") (pinfunction "2_5") (pintype "passive"))
    )
    (net (code "31") (name "Net-(FERRITE-Pad1)") (class "Default")
      (node (ref "FERRITE") (pin "1") (pinfunction "1_1") (pintype "passive"))
      (node (ref "FUSIBLE") (pin "2") (pinfunction "2_2") (pintype "passive"))
    )
    (net (code "32") (name "Net-(IC1-3V3OUT)") (class "Default")
      (node (ref "C7") (pin "1") (pinfunction "1_1") (pintype "passive"))
      (node (ref "IC1") (pin "17") (pinfunction "3V3OUT_17") (pintype "output"))
    )
    (net (code "33") (name "Net-(LV_LVLC1-DREF)") (class "Default")
      (node (ref "C1") (pin "1") (pinfunction "1_1") (pintype "passive"))
      (node (ref "LV_LVLC1") (pin "7") (pinfunction "DREF_7") (pintype "bidirectional"))
      (node (ref "LV_LVLC1") (pin "8") (pinfunction "GREF_8") (pintype "bidirectional"))
      (node (ref "R15") (pin "2") (pinfunction "2_2") (pintype "passive"))
    )
    (net (code "34") (name "Net-(LV_LVLC1-S1)") (class "Default")
      (node (ref "LV_LVLC1") (pin "3") (pinfunction "S1_3") (pintype "bidirectional"))
      (node (ref "X3") (pin "1") (pinfunction "1_1") (pintype "passive"))
    )
    (net (code "35") (name "Net-(LV_LVLC1-S2)") (class "Default")
      (node (ref "LV_LVLC1") (pin "4") (pinfunction "S2_4") (pintype "bidirectional"))
      (node (ref "X4") (pin "1") (pinfunction "1_1") (pintype "passive"))
    )
    (net (code "36") (name "Net-(LV_LVLC2-DREF)") (class "Default")
      (node (ref "C13") (pin "1") (pinfunction "1_1") (pintype "passive"))
      (node (ref "LV_LVLC2") (pin "7") (pinfunction "DREF_7") (pintype "bidirectional"))
      (node (ref "LV_LVLC2") (pin "8") (pinfunction "GREF_8") (pintype "bidirectional"))
      (node (ref "R71") (pin "2") (pinfunction "2_2") (pintype "passive"))
    )
    (net (code "37") (name "Net-(LV_LVLC2-S1)") (class "Default")
      (node (ref "LV_LVLC2") (pin "3") (pinfunction "S1_3") (pintype "bidirectional"))
      (node (ref "X1") (pin "1") (pinfunction "1_1") (pintype "passive"))
    )
    (net (code "38") (name "Net-(LV_LVLC2-S2)") (class "Default")
      (node (ref "LV_LVLC2") (pin "4") (pinfunction "S2_4") (pintype "bidirectional"))
      (node (ref "X2") (pin "1") (pinfunction "1_1") (pintype "passive"))
    )
    (net (code "39") (name "Net-(LV_LVLC3-DREF)") (class "Default")
      (node (ref "C3") (pin "1") (pinfunction "1_1") (pintype "passive"))
      (node (ref "LV_LVLC3") (pin "7") (pinfunction "DREF_7") (pintype "bidirectional"))
      (node (ref "LV_LVLC3") (pin "8") (pinfunction "GREF_8") (pintype "bidirectional"))
      (node (ref "R20") (pin "2") (pinfunction "2_2") (pintype "passive"))
    )
    (net (code "40") (name "Net-(LV_LVLC3-S1)") (class "Default")
      (node (ref "LV_LVLC3") (pin "3") (pinfunction "S1_3") (pintype "bidirectional"))
      (node (ref "X5") (pin "1") (pinfunction "1_1") (pintype "passive"))
    )
    (net (code "41") (name "Net-(LV_LVLC3-S2)") (class "Default")
      (node (ref "LV_LVLC3") (pin "4") (pinfunction "S2_4") (pintype "bidirectional"))
      (node (ref "X17") (pin "1") (pinfunction "1_1") (pintype "passive"))
    )
    (net (code "42") (name "Net-(LV_LVLC4-DREF)") (class "Default")
      (node (ref "C4") (pin "1") (pinfunction "1_1") (pintype "passive"))
      (node (ref "LV_LVLC4") (pin "7") (pinfunction "DREF_7") (pintype "bidirectional"))
      (node (ref "LV_LVLC4") (pin "8") (pinfunction "GREF_8") (pintype "bidirectional"))
      (node (ref "R23") (pin "2") (pinfunction "2_2") (pintype "passive"))
    )
    (net (code "43") (name "Net-(LV_LVLC4-S1)") (class "Default")
      (node (ref "LV_LVLC4") (pin "3") (pinfunction "S1_3") (pintype "bidirectional"))
      (node (ref "X18") (pin "1") (pinfunction "1_1") (pintype "passive"))
    )
    (net (code "44") (name "Net-(LV_LVLC4-S2)") (class "Default")
      (node (ref "LV_LVLC4") (pin "4") (pinfunction "S2_4") (pintype "bidirectional"))
      (node (ref "X19") (pin "1") (pinfunction "1_1") (pintype "passive"))
    )
    (net (code "45") (name "Net-(LV_LVLC5-DREF)") (class "Default")
      (node (ref "C14") (pin "1") (pinfunction "1_1") (pintype "passive"))
      (node (ref "LV_LVLC5") (pin "7") (pinfunction "DREF_7") (pintype "bidirectional"))
      (node (ref "LV_LVLC5") (pin "8") (pinfunction "GREF_8") (pintype "bidirectional"))
      (node (ref "R43") (pin "2") (pinfunction "2_2") (pintype "passive"))
    )
    (net (code "46") (name "Net-(LV_LVLC5-S1)") (class "Default")
      (node (ref "LV_LVLC5") (pin "3") (pinfunction "S1_3") (pintype "bidirectional"))
      (node (ref "X20") (pin "1") (pinfunction "1_1") (pintype "passive"))
    )
    (net (code "47") (name "Net-(LV_LVLC5-S2)") (class "Default")
      (node (ref "LV_LVLC5") (pin "4") (pinfunction "S2_4") (pintype "bidirectional"))
      (node (ref "X21") (pin "1") (pinfunction "1_1") (pintype "passive"))
    )
    (net (code "48") (name "Net-(LV_LVLC6-DREF)") (class "Default")
      (node (ref "C15") (pin "1") (pinfunction "1_1") (pintype "passive"))
      (node (ref "LV_LVLC6") (pin "7") (pinfunction "DREF_7") (pintype "bidirectional"))
      (node (ref "LV_LVLC6") (pin "8") (pinfunction "GREF_8") (pintype "bidirectional"))
      (node (ref "R46") (pin "2") (pinfunction "2_2") (pintype "passive"))
    )
    (net (code "49") (name "Net-(LV_LVLC6-S1)") (class "Default")
      (node (ref "LV_LVLC6") (pin "3") (pinfunction "S1_3") (pintype "bidirectional"))
      (node (ref "X22") (pin "1") (pinfunction "1_1") (pintype "passive"))
    )
    (net (code "50") (name "Net-(LV_LVLC6-S2)") (class "Default")
      (node (ref "LV_LVLC6") (pin "4") (pinfunction "S2_4") (pintype "bidirectional"))
      (node (ref "X23") (pin "1") (pinfunction "1_1") (pintype "passive"))
    )
    (net (code "51") (name "Net-(ON-PadA)") (class "Default")
      (node (ref "ON") (pin "A") (pinfunction "A_A") (pintype "passive"))
      (node (ref "R2") (pin "2") (pinfunction "2_2") (pintype "passive"))
    )
    (net (code "52") (name "Net-(R16-Pad2)") (class "Default")
      (node (ref "R16") (pin "2") (pinfunction "2_2") (pintype "passive"))
      (node (ref "TX") (pin "A") (pinfunction "A_A") (pintype "passive"))
    )
    (net (code "53") (name "Net-(R17-Pad2)") (class "Default")
      (node (ref "R17") (pin "2") (pinfunction "2_2") (pintype "passive"))
      (node (ref "RX") (pin "A") (pinfunction "A_A") (pintype "passive"))
    )
    (net (code "54") (name "Net-(U$1-OSC1{slash}CLKI{slash}RA7)") (class "Default")
      (node (ref "C11") (pin "1") (pinfunction "1_1") (pintype "passive"))
      (node (ref "Q1") (pin "1") (pinfunction "1_1") (pintype "passive"))
      (node (ref "U$1") (pin "9") (pinfunction "OSC1/CLKI/RA7_9") (pintype "bidirectional"))
    )
    (net (code "55") (name "Net-(U$1-OSC2{slash}CLKO{slash}RA6)") (class "Default")
      (node (ref "C12") (pin "1") (pinfunction "1_1") (pintype "passive"))
      (node (ref "Q1") (pin "2") (pinfunction "2_2") (pintype "passive"))
      (node (ref "U$1") (pin "10") (pinfunction "OSC2/CLKO/RA6_10") (pintype "bidirectional"))
    )
    (net (code "56") (name "unconnected-(IC1-CBUS2-Pad13)") (class "Default")
      (node (ref "IC1") (pin "13") (pinfunction "CBUS2_13") (pintype "bidirectional"))
    )
    (net (code "57") (name "unconnected-(IC1-CBUS3-Pad14)") (class "Default")
      (node (ref "IC1") (pin "14") (pinfunction "CBUS3_14") (pintype "bidirectional"))
    )
    (net (code "58") (name "unconnected-(IC1-CBUS4-Pad12)") (class "Default")
      (node (ref "IC1") (pin "12") (pinfunction "CBUS4_12") (pintype "bidirectional"))
    )
    (net (code "59") (name "unconnected-(IC1-OSCI-Pad27)") (class "Default")
      (node (ref "IC1") (pin "27") (pinfunction "OSCI_27") (pintype "input"))
    )
    (net (code "60") (name "unconnected-(IC1-OSCO-Pad28)") (class "Default")
      (node (ref "IC1") (pin "28") (pinfunction "OSCO_28") (pintype "output"))
    )
    (net (code "61") (name "unconnected-(IC1-~{CTS}-Pad11)") (class "Default")
      (node (ref "IC1") (pin "11") (pinfunction "~{CTS}_11") (pintype "input"))
    )
    (net (code "62") (name "unconnected-(IC1-~{DCD}-Pad10)") (class "Default")
      (node (ref "IC1") (pin "10") (pinfunction "~{DCD}_10") (pintype "input"))
    )
    (net (code "63") (name "unconnected-(IC1-~{DSR}-Pad9)") (class "Default")
      (node (ref "IC1") (pin "9") (pinfunction "~{DSR}_9") (pintype "input"))
    )
    (net (code "64") (name "unconnected-(IC1-~{DTR}-Pad2)") (class "Default")
      (node (ref "IC1") (pin "2") (pinfunction "~{DTR}_2") (pintype "output"))
    )
    (net (code "65") (name "unconnected-(IC1-~{RESET}-Pad19)") (class "Default")
      (node (ref "IC1") (pin "19") (pinfunction "~{RESET}_19") (pintype "input"))
    )
    (net (code "66") (name "unconnected-(IC1-~{RI}-Pad6)") (class "Default")
      (node (ref "IC1") (pin "6") (pinfunction "~{RI}_6") (pintype "input"))
    )
    (net (code "67") (name "unconnected-(IC1-~{RTS}-Pad3)") (class "Default")
      (node (ref "IC1") (pin "3") (pinfunction "~{RTS}_3") (pintype "output"))
    )
    (net (code "68") (name "unconnected-(J4-Pad4)") (class "Default")
      (node (ref "J4") (pin "4") (pinfunction "4_4") (pintype "input"))
    )
    (net (code "69") (name "unconnected-(U$1-RA0{slash}AN0-Pad2)") (class "Default")
      (node (ref "U$1") (pin "2") (pinfunction "RA0/AN0_2") (pintype "bidirectional"))
    )
    (net (code "70") (name "unconnected-(U$1-RA1{slash}AN1-Pad3)") (class "Default")
      (node (ref "U$1") (pin "3") (pinfunction "RA1/AN1_3") (pintype "bidirectional"))
    )
    (net (code "71") (name "unconnected-(U$1-RA2{slash}AN2{slash}VREF-{slash}CAP1{slash}INDX-Pad4)") (class "Default")
      (node (ref "U$1") (pin "4") (pinfunction "RA2/AN2/VREF-/CAP1/INDX_4") (pintype "bidirectional"))
    )
    (net (code "72") (name "unconnected-(U$1-RA3{slash}AN3{slash}VREF+{slash}CAP2{slash}QEA-Pad5)") (class "Default")
      (node (ref "U$1") (pin "5") (pinfunction "RA3/AN3/VREF+/CAP2/QEA_5") (pintype "bidirectional"))
    )
    (net (code "73") (name "unconnected-(U$1-RA4{slash}AN4{slash}CAP3{slash}QEB-Pad6)") (class "Default")
      (node (ref "U$1") (pin "6") (pinfunction "RA4/AN4/CAP3/QEB_6") (pintype "bidirectional"))
    )
    (net (code "74") (name "unconnected-(X14F-S-Pad6)") (class "Default")
      (node (ref "X14") (pin "6") (pinfunction "S_6") (pintype "passive"))
    )
  )
)
